# m201-stereo-input.net
KiCad netlist of a schematic drawn in EAGLE
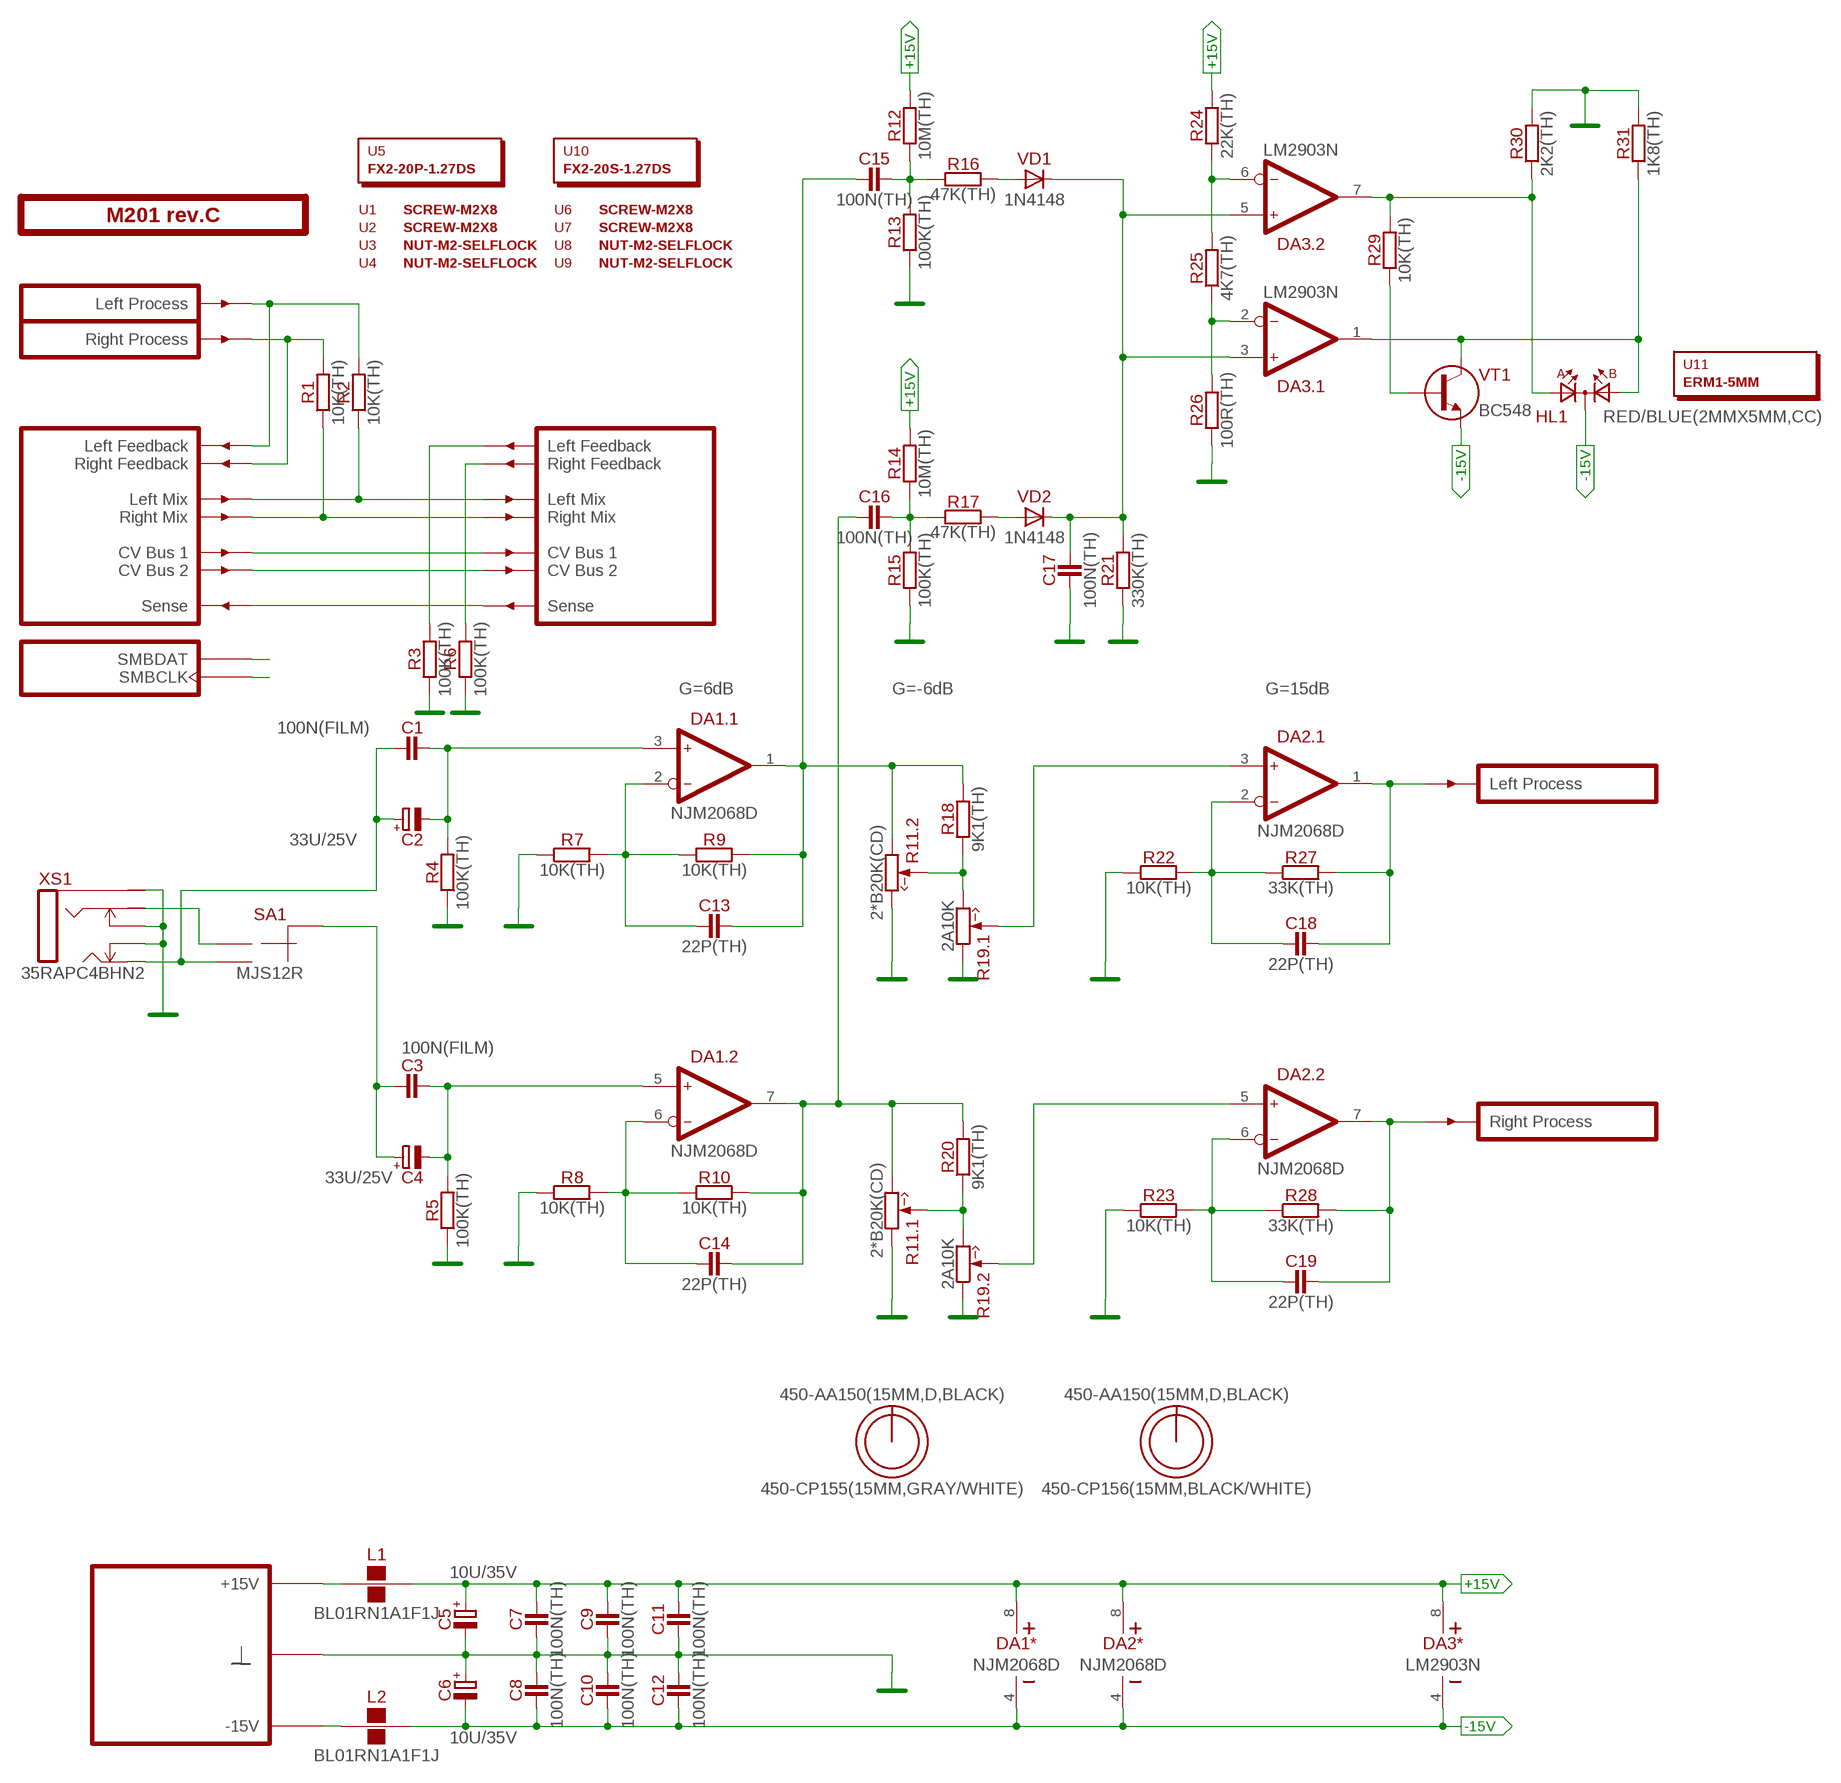
[diagram p0: schematic, sheet 1]

(export (version "E")
  (design (tool "Eeschema 10.0.6"))
  (components
    (comp (ref "C1")
      (value "100N(FILM)")
      (footprint "eagle-import:C050-025X075")
      (libsource (lib "eagle-import") (part "?100N(FILM)"))
    )
    (comp (ref "C2")
      (value "33U/25V")
      (footprint "eagle-import:E2,5-7")
      (libsource (lib "eagle-import") (part "?33U/25V"))
    )
    (comp (ref "C3")
      (value "100N(FILM)")
      (footprint "eagle-import:C050-025X075")
      (libsource (lib "eagle-import") (part "?100N(FILM)"))
    )
    (comp (ref "C4")
      (value "33U/25V")
      (footprint "eagle-import:E2,5-7")
      (libsource (lib "eagle-import") (part "?33U/25V"))
    )
    (comp (ref "C5")
      (value "10U/35V")
      (footprint "eagle-import:E2-5")
      (libsource (lib "eagle-import") (part "?10U/35V"))
    )
    (comp (ref "C6")
      (value "10U/35V")
      (footprint "eagle-import:E2-5")
      (libsource (lib "eagle-import") (part "?10U/35V"))
    )
    (comp (ref "C7")
      (value "100N(TH)")
      (footprint "eagle-import:C050-024X044")
      (libsource (lib "eagle-import") (part "?100N(TH)"))
    )
    (comp (ref "C8")
      (value "100N(TH)")
      (footprint "eagle-import:C050-024X044")
      (libsource (lib "eagle-import") (part "?100N(TH)"))
    )
    (comp (ref "C9")
      (value "100N(TH)")
      (footprint "eagle-import:C050-024X044")
      (libsource (lib "eagle-import") (part "?100N(TH)"))
    )
    (comp (ref "C10")
      (value "100N(TH)")
      (footprint "eagle-import:C050-024X044")
      (libsource (lib "eagle-import") (part "?100N(TH)"))
    )
    (comp (ref "C11")
      (value "100N(TH)")
      (footprint "eagle-import:C050-024X044")
      (libsource (lib "eagle-import") (part "?100N(TH)"))
    )
    (comp (ref "C12")
      (value "100N(TH)")
      (footprint "eagle-import:C050-024X044")
      (libsource (lib "eagle-import") (part "?100N(TH)"))
    )
    (comp (ref "C13")
      (value "22P(TH)")
      (footprint "eagle-import:C050-024X044")
      (libsource (lib "eagle-import") (part "?22P(TH)"))
    )
    (comp (ref "C14")
      (value "22P(TH)")
      (footprint "eagle-import:C050-024X044")
      (libsource (lib "eagle-import") (part "?22P(TH)"))
    )
    (comp (ref "C15")
      (value "100N(TH)")
      (footprint "eagle-import:C050-024X044")
      (libsource (lib "eagle-import") (part "?100N(TH)"))
    )
    (comp (ref "C16")
      (value "100N(TH)")
      (footprint "eagle-import:C050-024X044")
      (libsource (lib "eagle-import") (part "?100N(TH)"))
    )
    (comp (ref "C17")
      (value "100N(TH)")
      (footprint "eagle-import:C050-024X044")
      (libsource (lib "eagle-import") (part "?100N(TH)"))
    )
    (comp (ref "C18")
      (value "22P(TH)")
      (footprint "eagle-import:C050-024X044")
      (libsource (lib "eagle-import") (part "?22P(TH)"))
    )
    (comp (ref "C19")
      (value "22P(TH)")
      (footprint "eagle-import:C050-024X044")
      (libsource (lib "eagle-import") (part "?22P(TH)"))
    )
    (comp (ref "DA1")
      (value "NJM2068D")
      (footprint "eagle-import:DIP-8")
      (libsource (lib "eagle-import") (part "NJM2068D"))
    )
    (comp (ref "DA2")
      (value "NJM2068D")
      (footprint "eagle-import:DIP-8")
      (libsource (lib "eagle-import") (part "NJM2068D"))
    )
    (comp (ref "DA3")
      (value "LM2903N")
      (footprint "eagle-import:DIP-8")
      (libsource (lib "eagle-import") (part "LM2903N"))
    )
    (comp (ref "HL1")
      (value "RED/BLUE(2MMX5MM,CC)")
      (footprint "eagle-import:LED2X5-3PIN")
      (libsource (lib "eagle-import") (part "?(2MMX5MM,CC)RED/BLUE"))
    )
    (comp (ref "L1")
      (value "BL01RN1A1F1J")
      (footprint "eagle-import:BL01RN1A")
      (libsource (lib "eagle-import") (part "BL01RN1A?1F1J"))
    )
    (comp (ref "L2")
      (value "BL01RN1A1F1J")
      (footprint "eagle-import:BL01RN1A")
      (libsource (lib "eagle-import") (part "BL01RN1A?1F1J"))
    )
    (comp (ref "O1")
      (value "450-AA150(15MM,D,BLACK)")
      (footprint "eagle-import:EMPTY")
      (libsource (lib "eagle-import") (part "450-AA?150(15MM,D,BLACK)"))
    )
    (comp (ref "O2")
      (value "450-CP155(15MM,GRAY/WHITE)")
      (footprint "eagle-import:EMPTY")
      (libsource (lib "eagle-import") (part "450-C?P155(15MM,GRAY/WHITE)"))
    )
    (comp (ref "O3")
      (value "450-AA150(15MM,D,BLACK)")
      (footprint "eagle-import:EMPTY")
      (libsource (lib "eagle-import") (part "450-AA?150(15MM,D,BLACK)"))
    )
    (comp (ref "O4")
      (value "450-CP156(15MM,BLACK/WHITE)")
      (footprint "eagle-import:EMPTY")
      (libsource (lib "eagle-import") (part "450-C?P156(15MM,BLACK/WHITE)"))
    )
    (comp (ref "PCB1")
      (value "M201 rev.C")
      (footprint "eagle-import:ST2-BOARD-50")
      (libsource (lib "eagle-import") (part "ST2-BOARD-?50"))
    )
    (comp (ref "R1")
      (value "10K(TH)")
      (footprint "eagle-import:R-0207_10")
      (libsource (lib "eagle-import") (part "?10K(TH)"))
    )
    (comp (ref "R2")
      (value "10K(TH)")
      (footprint "eagle-import:R-0207_10")
      (libsource (lib "eagle-import") (part "?10K(TH)"))
    )
    (comp (ref "R3")
      (value "100K(TH)")
      (footprint "eagle-import:R-0207_10")
      (libsource (lib "eagle-import") (part "?100K(TH)"))
    )
    (comp (ref "R4")
      (value "100K(TH)")
      (footprint "eagle-import:R-0207_10")
      (libsource (lib "eagle-import") (part "?100K(TH)"))
    )
    (comp (ref "R5")
      (value "100K(TH)")
      (footprint "eagle-import:R-0207_10")
      (libsource (lib "eagle-import") (part "?100K(TH)"))
    )
    (comp (ref "R6")
      (value "100K(TH)")
      (footprint "eagle-import:R-0207_10")
      (libsource (lib "eagle-import") (part "?100K(TH)"))
    )
    (comp (ref "R7")
      (value "10K(TH)")
      (footprint "eagle-import:R-0207_10")
      (libsource (lib "eagle-import") (part "?10K(TH)"))
    )
    (comp (ref "R8")
      (value "10K(TH)")
      (footprint "eagle-import:R-0207_10")
      (libsource (lib "eagle-import") (part "?10K(TH)"))
    )
    (comp (ref "R9")
      (value "10K(TH)")
      (footprint "eagle-import:R-0207_10")
      (libsource (lib "eagle-import") (part "?10K(TH)"))
    )
    (comp (ref "R10")
      (value "10K(TH)")
      (footprint "eagle-import:R-0207_10")
      (libsource (lib "eagle-import") (part "?10K(TH)"))
    )
    (comp (ref "R11")
      (value "2*B20K(CD)")
      (footprint "eagle-import:RV11-DUAL")
      (libsource (lib "eagle-import") (part "2?B20K(CD)"))
    )
    (comp (ref "R12")
      (value "10M(TH)")
      (footprint "eagle-import:R-0207_10")
      (libsource (lib "eagle-import") (part "?10M(TH)"))
    )
    (comp (ref "R13")
      (value "100K(TH)")
      (footprint "eagle-import:R-0207_10")
      (libsource (lib "eagle-import") (part "?100K(TH)"))
    )
    (comp (ref "R14")
      (value "10M(TH)")
      (footprint "eagle-import:R-0207_10")
      (libsource (lib "eagle-import") (part "?10M(TH)"))
    )
    (comp (ref "R15")
      (value "100K(TH)")
      (footprint "eagle-import:R-0207_10")
      (libsource (lib "eagle-import") (part "?100K(TH)"))
    )
    (comp (ref "R16")
      (value "47K(TH)")
      (footprint "eagle-import:R-0207_10")
      (libsource (lib "eagle-import") (part "?47K(TH)"))
    )
    (comp (ref "R17")
      (value "47K(TH)")
      (footprint "eagle-import:R-0207_10")
      (libsource (lib "eagle-import") (part "?47K(TH)"))
    )
    (comp (ref "R18")
      (value "9K1(TH)")
      (footprint "eagle-import:R-0207_10")
      (libsource (lib "eagle-import") (part "?9K1(TH)"))
    )
    (comp (ref "R19")
      (value "2A10K")
      (footprint "eagle-import:RV11-DUAL")
      (libsource (lib "eagle-import") (part "2?A10K"))
    )
    (comp (ref "R20")
      (value "9K1(TH)")
      (footprint "eagle-import:R-0207_10")
      (libsource (lib "eagle-import") (part "?9K1(TH)"))
    )
    (comp (ref "R21")
      (value "330K(TH)")
      (footprint "eagle-import:R-0207_10")
      (libsource (lib "eagle-import") (part "?330K(TH)"))
    )
    (comp (ref "R22")
      (value "10K(TH)")
      (footprint "eagle-import:R-0207_10")
      (libsource (lib "eagle-import") (part "?10K(TH)"))
    )
    (comp (ref "R23")
      (value "10K(TH)")
      (footprint "eagle-import:R-0207_10")
      (libsource (lib "eagle-import") (part "?10K(TH)"))
    )
    (comp (ref "R24")
      (value "22K(TH)")
      (footprint "eagle-import:R-0207_10")
      (libsource (lib "eagle-import") (part "?22K(TH)"))
    )
    (comp (ref "R25")
      (value "4K7(TH)")
      (footprint "eagle-import:R-0207_10")
      (libsource (lib "eagle-import") (part "?4K7(TH)"))
    )
    (comp (ref "R26")
      (value "100R(TH)")
      (footprint "eagle-import:R-0207_10")
      (libsource (lib "eagle-import") (part "?100R(TH)"))
    )
    (comp (ref "R27")
      (value "33K(TH)")
      (footprint "eagle-import:R-0207_10")
      (libsource (lib "eagle-import") (part "?33K(TH)"))
    )
    (comp (ref "R28")
      (value "33K(TH)")
      (footprint "eagle-import:R-0207_10")
      (libsource (lib "eagle-import") (part "?33K(TH)"))
    )
    (comp (ref "R29")
      (value "10K(TH)")
      (footprint "eagle-import:R-0207_10")
      (libsource (lib "eagle-import") (part "?10K(TH)"))
    )
    (comp (ref "R30")
      (value "2K2(TH)")
      (footprint "eagle-import:R-0207_10")
      (libsource (lib "eagle-import") (part "?2K2(TH)"))
    )
    (comp (ref "R31")
      (value "1K8(TH)")
      (footprint "eagle-import:R-0207_10")
      (libsource (lib "eagle-import") (part "?1K8(TH)"))
    )
    (comp (ref "SA1")
      (value "MJS12R")
      (footprint "eagle-import:APEM-MJS12R")
      (libsource (lib "eagle-import") (part "MJS12R"))
    )
    (comp (ref "U1")
      (value "SCREW-M2X8")
      (footprint "eagle-import:EMPTY")
      (libsource (lib "eagle-import") (part "?SCREW-M2X8"))
    )
    (comp (ref "U2")
      (value "SCREW-M2X8")
      (footprint "eagle-import:EMPTY")
      (libsource (lib "eagle-import") (part "?SCREW-M2X8"))
    )
    (comp (ref "U3")
      (value "NUT-M2-SELFLOCK")
      (footprint "eagle-import:EMPTY")
      (libsource (lib "eagle-import") (part "?NUT-M2-SELFLOCK"))
    )
    (comp (ref "U4")
      (value "NUT-M2-SELFLOCK")
      (footprint "eagle-import:EMPTY")
      (libsource (lib "eagle-import") (part "?NUT-M2-SELFLOCK"))
    )
    (comp (ref "U5")
      (value "FX2-20P-1.27DS")
      (footprint "eagle-import:EMPTY")
      (libsource (lib "eagle-import") (part "?FX2-20P-1.27DS"))
    )
    (comp (ref "U6")
      (value "SCREW-M2X8")
      (footprint "eagle-import:EMPTY")
      (libsource (lib "eagle-import") (part "?SCREW-M2X8"))
    )
    (comp (ref "U7")
      (value "SCREW-M2X8")
      (footprint "eagle-import:EMPTY")
      (libsource (lib "eagle-import") (part "?SCREW-M2X8"))
    )
    (comp (ref "U8")
      (value "NUT-M2-SELFLOCK")
      (footprint "eagle-import:EMPTY")
      (libsource (lib "eagle-import") (part "?NUT-M2-SELFLOCK"))
    )
    (comp (ref "U9")
      (value "NUT-M2-SELFLOCK")
      (footprint "eagle-import:EMPTY")
      (libsource (lib "eagle-import") (part "?NUT-M2-SELFLOCK"))
    )
    (comp (ref "U10")
      (value "FX2-20S-1.27DS")
      (footprint "eagle-import:EMPTY")
      (libsource (lib "eagle-import") (part "?FX2-20S-1.27DS"))
    )
    (comp (ref "U11")
      (value "ERM1-5MM")
      (footprint "eagle-import:EMPTY")
      (libsource (lib "eagle-import") (part "?ERM1-5MM"))
    )
    (comp (ref "VD1")
      (value "1N4148")
      (footprint "eagle-import:DO35-7")
      (libsource (lib "eagle-import") (part "?1N4148"))
    )
    (comp (ref "VD2")
      (value "1N4148")
      (footprint "eagle-import:DO35-7")
      (libsource (lib "eagle-import") (part "?1N4148"))
    )
    (comp (ref "VT1")
      (value "BC548")
      (footprint "eagle-import:TO92")
      (libsource (lib "eagle-import") (part "?BC548"))
    )
    (comp (ref "XS1")
      (value "35RAPC4BHN2")
      (footprint "eagle-import:35RAP")
      (libsource (lib "eagle-import") (part "35RAPC4BHN2"))
    )
  )
  (nets
    (net (code "1") (name "+15V") (class "Default")
      (node (ref "C11") (pin "2") (pinfunction "2_2") (pintype "passive"))
      (node (ref "C5") (pin "+") (pinfunction "+_+") (pintype "passive"))
      (node (ref "C7") (pin "2") (pinfunction "2_2") (pintype "passive"))
      (node (ref "C9") (pin "2") (pinfunction "2_2") (pintype "passive"))
      (node (ref "DA1") (pin "8") (pinfunction "V+_8") (pintype "power_in"))
      (node (ref "DA2") (pin "8") (pinfunction "V+_8") (pintype "power_in"))
      (node (ref "DA3") (pin "8") (pinfunction "V+_8") (pintype "power_in"))
      (node (ref "L1") (pin "2") (pinfunction "2_2") (pintype "passive"))
      (node (ref "R12") (pin "2") (pinfunction "2_2") (pintype "passive"))
      (node (ref "R14") (pin "2") (pinfunction "2_2") (pintype "passive"))
      (node (ref "R24") (pin "2") (pinfunction "2_2") (pintype "passive"))
    )
    (net (code "2") (name "-15V") (class "Default")
      (node (ref "C10") (pin "1") (pinfunction "1_1") (pintype "passive"))
      (node (ref "C12") (pin "1") (pinfunction "1_1") (pintype "passive"))
      (node (ref "C6") (pin "-") (pinfunction "-_-") (pintype "passive"))
      (node (ref "C8") (pin "1") (pinfunction "1_1") (pintype "passive"))
      (node (ref "DA1") (pin "4") (pinfunction "V-_4") (pintype "power_in"))
      (node (ref "DA2") (pin "4") (pinfunction "V-_4") (pintype "power_in"))
      (node (ref "DA3") (pin "4") (pinfunction "V-_4") (pintype "power_in"))
      (node (ref "HL1") (pin "K") (pinfunction "K_K") (pintype "passive"))
      (node (ref "L2") (pin "2") (pinfunction "2_2") (pintype "passive"))
      (node (ref "VT1") (pin "3") (pinfunction "E_3") (pintype "passive"))
    )
    (net (code "3") (name "GND") (class "Default")
      (node (ref "C10") (pin "2") (pinfunction "2_2") (pintype "passive"))
      (node (ref "C11") (pin "1") (pinfunction "1_1") (pintype "passive"))
      (node (ref "C12") (pin "2") (pinfunction "2_2") (pintype "passive"))
      (node (ref "C17") (pin "1") (pinfunction "1_1") (pintype "passive"))
      (node (ref "C5") (pin "-") (pinfunction "-_-") (pintype "passive"))
      (node (ref "C6") (pin "+") (pinfunction "+_+") (pintype "passive"))
      (node (ref "C7") (pin "1") (pinfunction "1_1") (pintype "passive"))
      (node (ref "C8") (pin "2") (pinfunction "2_2") (pintype "passive"))
      (node (ref "C9") (pin "1") (pinfunction "1_1") (pintype "passive"))
      (node (ref "PCB1") (pin "B4") (pinfunction "GND_B4") (pintype "bidirectional"))
      (node (ref "PCB1") (pin "B4'") (pinfunction "GND_B4'") (pintype "bidirectional"))
      (node (ref "PCB1") (pin "B5") (pinfunction "GND_B5") (pintype "bidirectional"))
      (node (ref "PCB1") (pin "B5'") (pinfunction "GND_B5'") (pintype "bidirectional"))
      (node (ref "PCB1") (pin "B6") (pinfunction "GND_B6") (pintype "bidirectional"))
      (node (ref "PCB1") (pin "B6'") (pinfunction "GND_B6'") (pintype "bidirectional"))
      (node (ref "PCB1") (pin "B7") (pinfunction "GND_B7") (pintype "bidirectional"))
      (node (ref "PCB1") (pin "B7'") (pinfunction "GND_B7'") (pintype "bidirectional"))
      (node (ref "PCB1") (pin "B8") (pinfunction "GND_B8") (pintype "bidirectional"))
      (node (ref "PCB1") (pin "B8'") (pinfunction "GND_B8'") (pintype "bidirectional"))
      (node (ref "R11") (pin "1") (pinfunction "CCW_1") (pintype "passive"))
      (node (ref "R11") (pin "3'") (pinfunction "CW_3'") (pintype "passive"))
      (node (ref "R13") (pin "1") (pinfunction "1_1") (pintype "passive"))
      (node (ref "R15") (pin "1") (pinfunction "1_1") (pintype "passive"))
      (node (ref "R19") (pin "1") (pinfunction "CCW_1") (pintype "passive"))
      (node (ref "R19") (pin "1'") (pinfunction "CCW_1'") (pintype "passive"))
      (node (ref "R21") (pin "1") (pinfunction "1_1") (pintype "passive"))
      (node (ref "R22") (pin "1") (pinfunction "1_1") (pintype "passive"))
      (node (ref "R23") (pin "1") (pinfunction "1_1") (pintype "passive"))
      (node (ref "R26") (pin "1") (pinfunction "1_1") (pintype "passive"))
      (node (ref "R3") (pin "1") (pinfunction "1_1") (pintype "passive"))
      (node (ref "R30") (pin "2") (pinfunction "2_2") (pintype "passive"))
      (node (ref "R31") (pin "2") (pinfunction "2_2") (pintype "passive"))
      (node (ref "R4") (pin "1") (pinfunction "1_1") (pintype "passive"))
      (node (ref "R5") (pin "1") (pinfunction "1_1") (pintype "passive"))
      (node (ref "R6") (pin "1") (pinfunction "1_1") (pintype "passive"))
      (node (ref "R7") (pin "1") (pinfunction "1_1") (pintype "passive"))
      (node (ref "R8") (pin "1") (pinfunction "1_1") (pintype "passive"))
      (node (ref "XS1") (pin "1") (pinfunction "S_1") (pintype "passive"))
      (node (ref "XS1") (pin "10") (pinfunction "TN_10") (pintype "passive"))
      (node (ref "XS1") (pin "11") (pinfunction "RN_11") (pintype "passive"))
    )
    (net (code "4") (name "Net-(C15-Pad2)") (class "Default")
      (node (ref "C15") (pin "2") (pinfunction "2_2") (pintype "passive"))
      (node (ref "R12") (pin "1") (pinfunction "1_1") (pintype "passive"))
      (node (ref "R13") (pin "2") (pinfunction "2_2") (pintype "passive"))
      (node (ref "R16") (pin "1") (pinfunction "1_1") (pintype "passive"))
    )
    (net (code "5") (name "Net-(C16-Pad2)") (class "Default")
      (node (ref "C16") (pin "2") (pinfunction "2_2") (pintype "passive"))
      (node (ref "R14") (pin "1") (pinfunction "1_1") (pintype "passive"))
      (node (ref "R15") (pin "2") (pinfunction "2_2") (pintype "passive"))
      (node (ref "R17") (pin "1") (pinfunction "1_1") (pintype "passive"))
    )
    (net (code "6") (name "Net-(DA1B-IN+)") (class "Default")
      (node (ref "C1") (pin "2") (pinfunction "2_2") (pintype "passive"))
      (node (ref "C2") (pin "-") (pinfunction "-_-") (pintype "passive"))
      (node (ref "DA1") (pin "3") (pinfunction "IN+_3") (pintype "input"))
      (node (ref "R4") (pin "2") (pinfunction "2_2") (pintype "passive"))
    )
    (net (code "7") (name "Net-(DA1B-IN-)") (class "Default")
      (node (ref "C13") (pin "1") (pinfunction "1_1") (pintype "passive"))
      (node (ref "DA1") (pin "2") (pinfunction "IN-_2") (pintype "input"))
      (node (ref "R7") (pin "2") (pinfunction "2_2") (pintype "passive"))
      (node (ref "R9") (pin "1") (pinfunction "1_1") (pintype "passive"))
    )
    (net (code "8") (name "Net-(DA1B-OUT)") (class "Default")
      (node (ref "C13") (pin "2") (pinfunction "2_2") (pintype "passive"))
      (node (ref "C15") (pin "1") (pinfunction "1_1") (pintype "passive"))
      (node (ref "DA1") (pin "1") (pinfunction "OUT_1") (pintype "output"))
      (node (ref "R11") (pin "1'") (pinfunction "CCW_1'") (pintype "passive"))
      (node (ref "R18") (pin "2") (pinfunction "2_2") (pintype "passive"))
      (node (ref "R9") (pin "2") (pinfunction "2_2") (pintype "passive"))
    )
    (net (code "9") (name "Net-(DA1C-IN+)") (class "Default")
      (node (ref "C3") (pin "2") (pinfunction "2_2") (pintype "passive"))
      (node (ref "C4") (pin "-") (pinfunction "-_-") (pintype "passive"))
      (node (ref "DA1") (pin "5") (pinfunction "IN+_5") (pintype "input"))
      (node (ref "R5") (pin "2") (pinfunction "2_2") (pintype "passive"))
    )
    (net (code "10") (name "Net-(DA1C-IN-)") (class "Default")
      (node (ref "C14") (pin "1") (pinfunction "1_1") (pintype "passive"))
      (node (ref "DA1") (pin "6") (pinfunction "IN-_6") (pintype "input"))
      (node (ref "R10") (pin "1") (pinfunction "1_1") (pintype "passive"))
      (node (ref "R8") (pin "2") (pinfunction "2_2") (pintype "passive"))
    )
    (net (code "11") (name "Net-(DA1C-OUT)") (class "Default")
      (node (ref "C14") (pin "2") (pinfunction "2_2") (pintype "passive"))
      (node (ref "C16") (pin "1") (pinfunction "1_1") (pintype "passive"))
      (node (ref "DA1") (pin "7") (pinfunction "OUT_7") (pintype "output"))
      (node (ref "R10") (pin "2") (pinfunction "2_2") (pintype "passive"))
      (node (ref "R11") (pin "3") (pinfunction "CW_3") (pintype "passive"))
      (node (ref "R20") (pin "2") (pinfunction "2_2") (pintype "passive"))
    )
    (net (code "12") (name "Net-(DA2B-IN+)") (class "Default")
      (node (ref "DA2") (pin "3") (pinfunction "IN+_3") (pintype "input"))
      (node (ref "R19") (pin "2") (pinfunction "W_2") (pintype "passive"))
    )
    (net (code "13") (name "Net-(DA2B-IN-)") (class "Default")
      (node (ref "C18") (pin "1") (pinfunction "1_1") (pintype "passive"))
      (node (ref "DA2") (pin "2") (pinfunction "IN-_2") (pintype "input"))
      (node (ref "R22") (pin "2") (pinfunction "2_2") (pintype "passive"))
      (node (ref "R27") (pin "1") (pinfunction "1_1") (pintype "passive"))
    )
    (net (code "14") (name "Net-(DA2B-OUT)") (class "Default")
      (node (ref "C18") (pin "2") (pinfunction "2_2") (pintype "passive"))
      (node (ref "DA2") (pin "1") (pinfunction "OUT_1") (pintype "output"))
      (node (ref "PCB1") (pin "BOUTL'") (pinfunction "OUTL_BOUTL'") (pintype "bidirectional"))
      (node (ref "R27") (pin "2") (pinfunction "2_2") (pintype "passive"))
    )
    (net (code "15") (name "Net-(DA2C-IN+)") (class "Default")
      (node (ref "DA2") (pin "5") (pinfunction "IN+_5") (pintype "input"))
      (node (ref "R19") (pin "2'") (pinfunction "W_2'") (pintype "passive"))
    )
    (net (code "16") (name "Net-(DA2C-IN-)") (class "Default")
      (node (ref "C19") (pin "1") (pinfunction "1_1") (pintype "passive"))
      (node (ref "DA2") (pin "6") (pinfunction "IN-_6") (pintype "input"))
      (node (ref "R23") (pin "2") (pinfunction "2_2") (pintype "passive"))
      (node (ref "R28") (pin "1") (pinfunction "1_1") (pintype "passive"))
    )
    (net (code "17") (name "Net-(DA2C-OUT)") (class "Default")
      (node (ref "C19") (pin "2") (pinfunction "2_2") (pintype "passive"))
      (node (ref "DA2") (pin "7") (pinfunction "OUT_7") (pintype "output"))
      (node (ref "PCB1") (pin "BOUTR'") (pinfunction "OUTR_BOUTR'") (pintype "bidirectional"))
      (node (ref "R28") (pin "2") (pinfunction "2_2") (pintype "passive"))
    )
    (net (code "18") (name "Net-(DA3B-IN+)") (class "Default")
      (node (ref "C17") (pin "2") (pinfunction "2_2") (pintype "passive"))
      (node (ref "DA3") (pin "3") (pinfunction "IN+_3") (pintype "input"))
      (node (ref "DA3") (pin "5") (pinfunction "IN+_5") (pintype "input"))
      (node (ref "R21") (pin "2") (pinfunction "2_2") (pintype "passive"))
      (node (ref "VD1") (pin "C") (pinfunction "C_C") (pintype "passive"))
      (node (ref "VD2") (pin "C") (pinfunction "C_C") (pintype "passive"))
    )
    (net (code "19") (name "Net-(DA3B-IN-)") (class "Default")
      (node (ref "DA3") (pin "2") (pinfunction "IN-_2") (pintype "input"))
      (node (ref "R25") (pin "1") (pinfunction "1_1") (pintype "passive"))
      (node (ref "R26") (pin "2") (pinfunction "2_2") (pintype "passive"))
    )
    (net (code "20") (name "Net-(DA3B-OUT)") (class "Default")
      (node (ref "DA3") (pin "1") (pinfunction "OUT_1") (pintype "output"))
      (node (ref "HL1") (pin "A2") (pinfunction "A2_A2") (pintype "passive"))
      (node (ref "R31") (pin "1") (pinfunction "1_1") (pintype "passive"))
      (node (ref "VT1") (pin "1") (pinfunction "C_1") (pintype "passive"))
    )
    (net (code "21") (name "Net-(DA3C-IN-)") (class "Default")
      (node (ref "DA3") (pin "6") (pinfunction "IN-_6") (pintype "input"))
      (node (ref "R24") (pin "1") (pinfunction "1_1") (pintype "passive"))
      (node (ref "R25") (pin "2") (pinfunction "2_2") (pintype "passive"))
    )
    (net (code "22") (name "Net-(DA3C-OUT)") (class "Default")
      (node (ref "DA3") (pin "7") (pinfunction "OUT_7") (pintype "output"))
      (node (ref "HL1") (pin "A1") (pinfunction "A1_A1") (pintype "passive"))
      (node (ref "R29") (pin "2") (pinfunction "2_2") (pintype "passive"))
      (node (ref "R30") (pin "1") (pinfunction "1_1") (pintype "passive"))
    )
    (net (code "23") (name "Net-(L1-Pad1)") (class "Default")
      (node (ref "L1") (pin "1") (pinfunction "1_1") (pintype "passive"))
      (node (ref "PCB1") (pin "A+15") (pinfunction "P+15V_A+15") (pintype "bidirectional"))
      (node (ref "PCB1") (pin "A+15'") (pinfunction "P+15V_A+15'") (pintype "bidirectional"))
      (node (ref "PCB1") (pin "B+15") (pinfunction "P+15V_B+15") (pintype "bidirectional"))
      (node (ref "PCB1") (pin "B+15'") (pinfunction "P+15V_B+15'") (pintype "bidirectional"))
    )
    (net (code "24") (name "Net-(L2-Pad1)") (class "Default")
      (node (ref "L2") (pin "1") (pinfunction "1_1") (pintype "passive"))
      (node (ref "PCB1") (pin "A-15") (pinfunction "P-15V_A-15") (pintype "bidirectional"))
      (node (ref "PCB1") (pin "A-15'") (pinfunction "P-15V_A-15'") (pintype "bidirectional"))
      (node (ref "PCB1") (pin "B-15") (pinfunction "P-15V_B-15") (pintype "bidirectional"))
      (node (ref "PCB1") (pin "B-15'") (pinfunction "P-15V_B-15'") (pintype "bidirectional"))
    )
    (net (code "25") (name "Net-(PCB1B-INL)") (class "Default")
      (node (ref "PCB1") (pin "ALFBK") (pinfunction "LFBK_ALFBK") (pintype "bidirectional"))
      (node (ref "PCB1") (pin "BINL") (pinfunction "INL_BINL") (pintype "bidirectional"))
      (node (ref "R2") (pin "2") (pinfunction "2_2") (pintype "passive"))
    )
    (net (code "26") (name "Net-(PCB1C-INR)") (class "Default")
      (node (ref "PCB1") (pin "ARFBK") (pinfunction "RFBK_ARFBK") (pintype "bidirectional"))
      (node (ref "PCB1") (pin "BINR") (pinfunction "INR_BINR") (pintype "bidirectional"))
      (node (ref "R1") (pin "2") (pinfunction "2_2") (pintype "passive"))
    )
    (net (code "27") (name "Net-(PCB1F-CV1)") (class "Default")
      (node (ref "PCB1") (pin "ACV1") (pinfunction "CV1_ACV1") (pintype "bidirectional"))
      (node (ref "PCB1") (pin "ACV1'") (pinfunction "CV1'_ACV1'") (pintype "bidirectional"))
    )
    (net (code "28") (name "Net-(PCB1F-CV2)") (class "Default")
      (node (ref "PCB1") (pin "ACV2") (pinfunction "CV2_ACV2") (pintype "bidirectional"))
      (node (ref "PCB1") (pin "ACV2'") (pinfunction "CV2'_ACV2'") (pintype "bidirectional"))
    )
    (net (code "29") (name "Net-(PCB1F-LMIX)") (class "Default")
      (node (ref "PCB1") (pin "ALMIX") (pinfunction "LMIX_ALMIX") (pintype "bidirectional"))
      (node (ref "PCB1") (pin "ALMIX'") (pinfunction "LMIX'_ALMIX'") (pintype "bidirectional"))
      (node (ref "R2") (pin "1") (pinfunction "1_1") (pintype "passive"))
    )
    (net (code "30") (name "Net-(PCB1F-RMIX)") (class "Default")
      (node (ref "PCB1") (pin "ARMIX") (pinfunction "RMIX_ARMIX") (pintype "bidirectional"))
      (node (ref "PCB1") (pin "ARMIX'") (pinfunction "RMIX'_ARMIX'") (pintype "bidirectional"))
      (node (ref "R1") (pin "1") (pinfunction "1_1") (pintype "passive"))
    )
    (net (code "31") (name "Net-(PCB1F-SENSE)") (class "Default")
      (node (ref "PCB1") (pin "BSENSE") (pinfunction "SENSE_BSENSE") (pintype "bidirectional"))
      (node (ref "PCB1") (pin "BSENSE'") (pinfunction "SENSE'_BSENSE'") (pintype "bidirectional"))
    )
    (net (code "32") (name "Net-(PCB1G-LFBK')") (class "Default")
      (node (ref "PCB1") (pin "ALFBK'") (pinfunction "LFBK'_ALFBK'") (pintype "bidirectional"))
      (node (ref "R3") (pin "2") (pinfunction "2_2") (pintype "passive"))
    )
    (net (code "33") (name "Net-(PCB1G-RFBK')") (class "Default")
      (node (ref "PCB1") (pin "ARFBK'") (pinfunction "RFBK'_ARFBK'") (pintype "bidirectional"))
      (node (ref "R6") (pin "2") (pinfunction "2_2") (pintype "passive"))
    )
    (net (code "34") (name "Net-(PCB1H-SMBCLK-PadASMBCLK')") (class "Default")
      (node (ref "PCB1") (pin "ASMBCLK") (pinfunction "SMBCLK_ASMBCLK") (pintype "bidirectional"))
      (node (ref "PCB1") (pin "ASMBCLK'") (pinfunction "SMBCLK_ASMBCLK'") (pintype "bidirectional"))
    )
    (net (code "35") (name "Net-(PCB1H-SMBDAT-PadASMBDAT')") (class "Default")
      (node (ref "PCB1") (pin "ASMBDAT") (pinfunction "SMBDAT_ASMBDAT") (pintype "bidirectional"))
      (node (ref "PCB1") (pin "ASMBDAT'") (pinfunction "SMBDAT_ASMBDAT'") (pintype "bidirectional"))
    )
    (net (code "36") (name "Net-(R11A-W)") (class "Default")
      (node (ref "R11") (pin "2") (pinfunction "W_2") (pintype "passive"))
      (node (ref "R19") (pin "3'") (pinfunction "CW_3'") (pintype "passive"))
      (node (ref "R20") (pin "1") (pinfunction "1_1") (pintype "passive"))
    )
    (net (code "37") (name "Net-(R11B-W)") (class "Default")
      (node (ref "R11") (pin "2'") (pinfunction "W_2'") (pintype "passive"))
      (node (ref "R18") (pin "1") (pinfunction "1_1") (pintype "passive"))
      (node (ref "R19") (pin "3") (pinfunction "CW_3") (pintype "passive"))
    )
    (net (code "38") (name "Net-(R16-Pad2)") (class "Default")
      (node (ref "R16") (pin "2") (pinfunction "2_2") (pintype "passive"))
      (node (ref "VD1") (pin "A") (pinfunction "A_A") (pintype "passive"))
    )
    (net (code "39") (name "Net-(R17-Pad2)") (class "Default")
      (node (ref "R17") (pin "2") (pinfunction "2_2") (pintype "passive"))
      (node (ref "VD2") (pin "A") (pinfunction "A_A") (pintype "passive"))
    )
    (net (code "40") (name "Net-(SA1-1)") (class "Default")
      (node (ref "SA1") (pin "NC") (pinfunction "1_NC") (pintype "passive"))
      (node (ref "XS1") (pin "3") (pinfunction "R_3") (pintype "passive"))
    )
    (net (code "41") (name "Net-(SA1-2)") (class "Default")
      (node (ref "C1") (pin "1") (pinfunction "1_1") (pintype "passive"))
      (node (ref "C2") (pin "+") (pinfunction "+_+") (pintype "passive"))
      (node (ref "SA1") (pin "NO") (pinfunction "2_NO") (pintype "passive"))
      (node (ref "XS1") (pin "2") (pinfunction "T_2") (pintype "passive"))
    )
    (net (code "42") (name "Net-(SA1-CM)") (class "Default")
      (node (ref "C3") (pin "1") (pinfunction "1_1") (pintype "passive"))
      (node (ref "C4") (pin "+") (pinfunction "+_+") (pintype "passive"))
      (node (ref "SA1") (pin "C") (pinfunction "CM_C") (pintype "passive"))
    )
    (net (code "43") (name "Net-(VT1-B)") (class "Default")
      (node (ref "R29") (pin "1") (pinfunction "1_1") (pintype "passive"))
      (node (ref "VT1") (pin "2") (pinfunction "B_2") (pintype "passive"))
    )
  )
)
